# untitled2.net
KiCad netlist of a schematic drawn in EAGLE
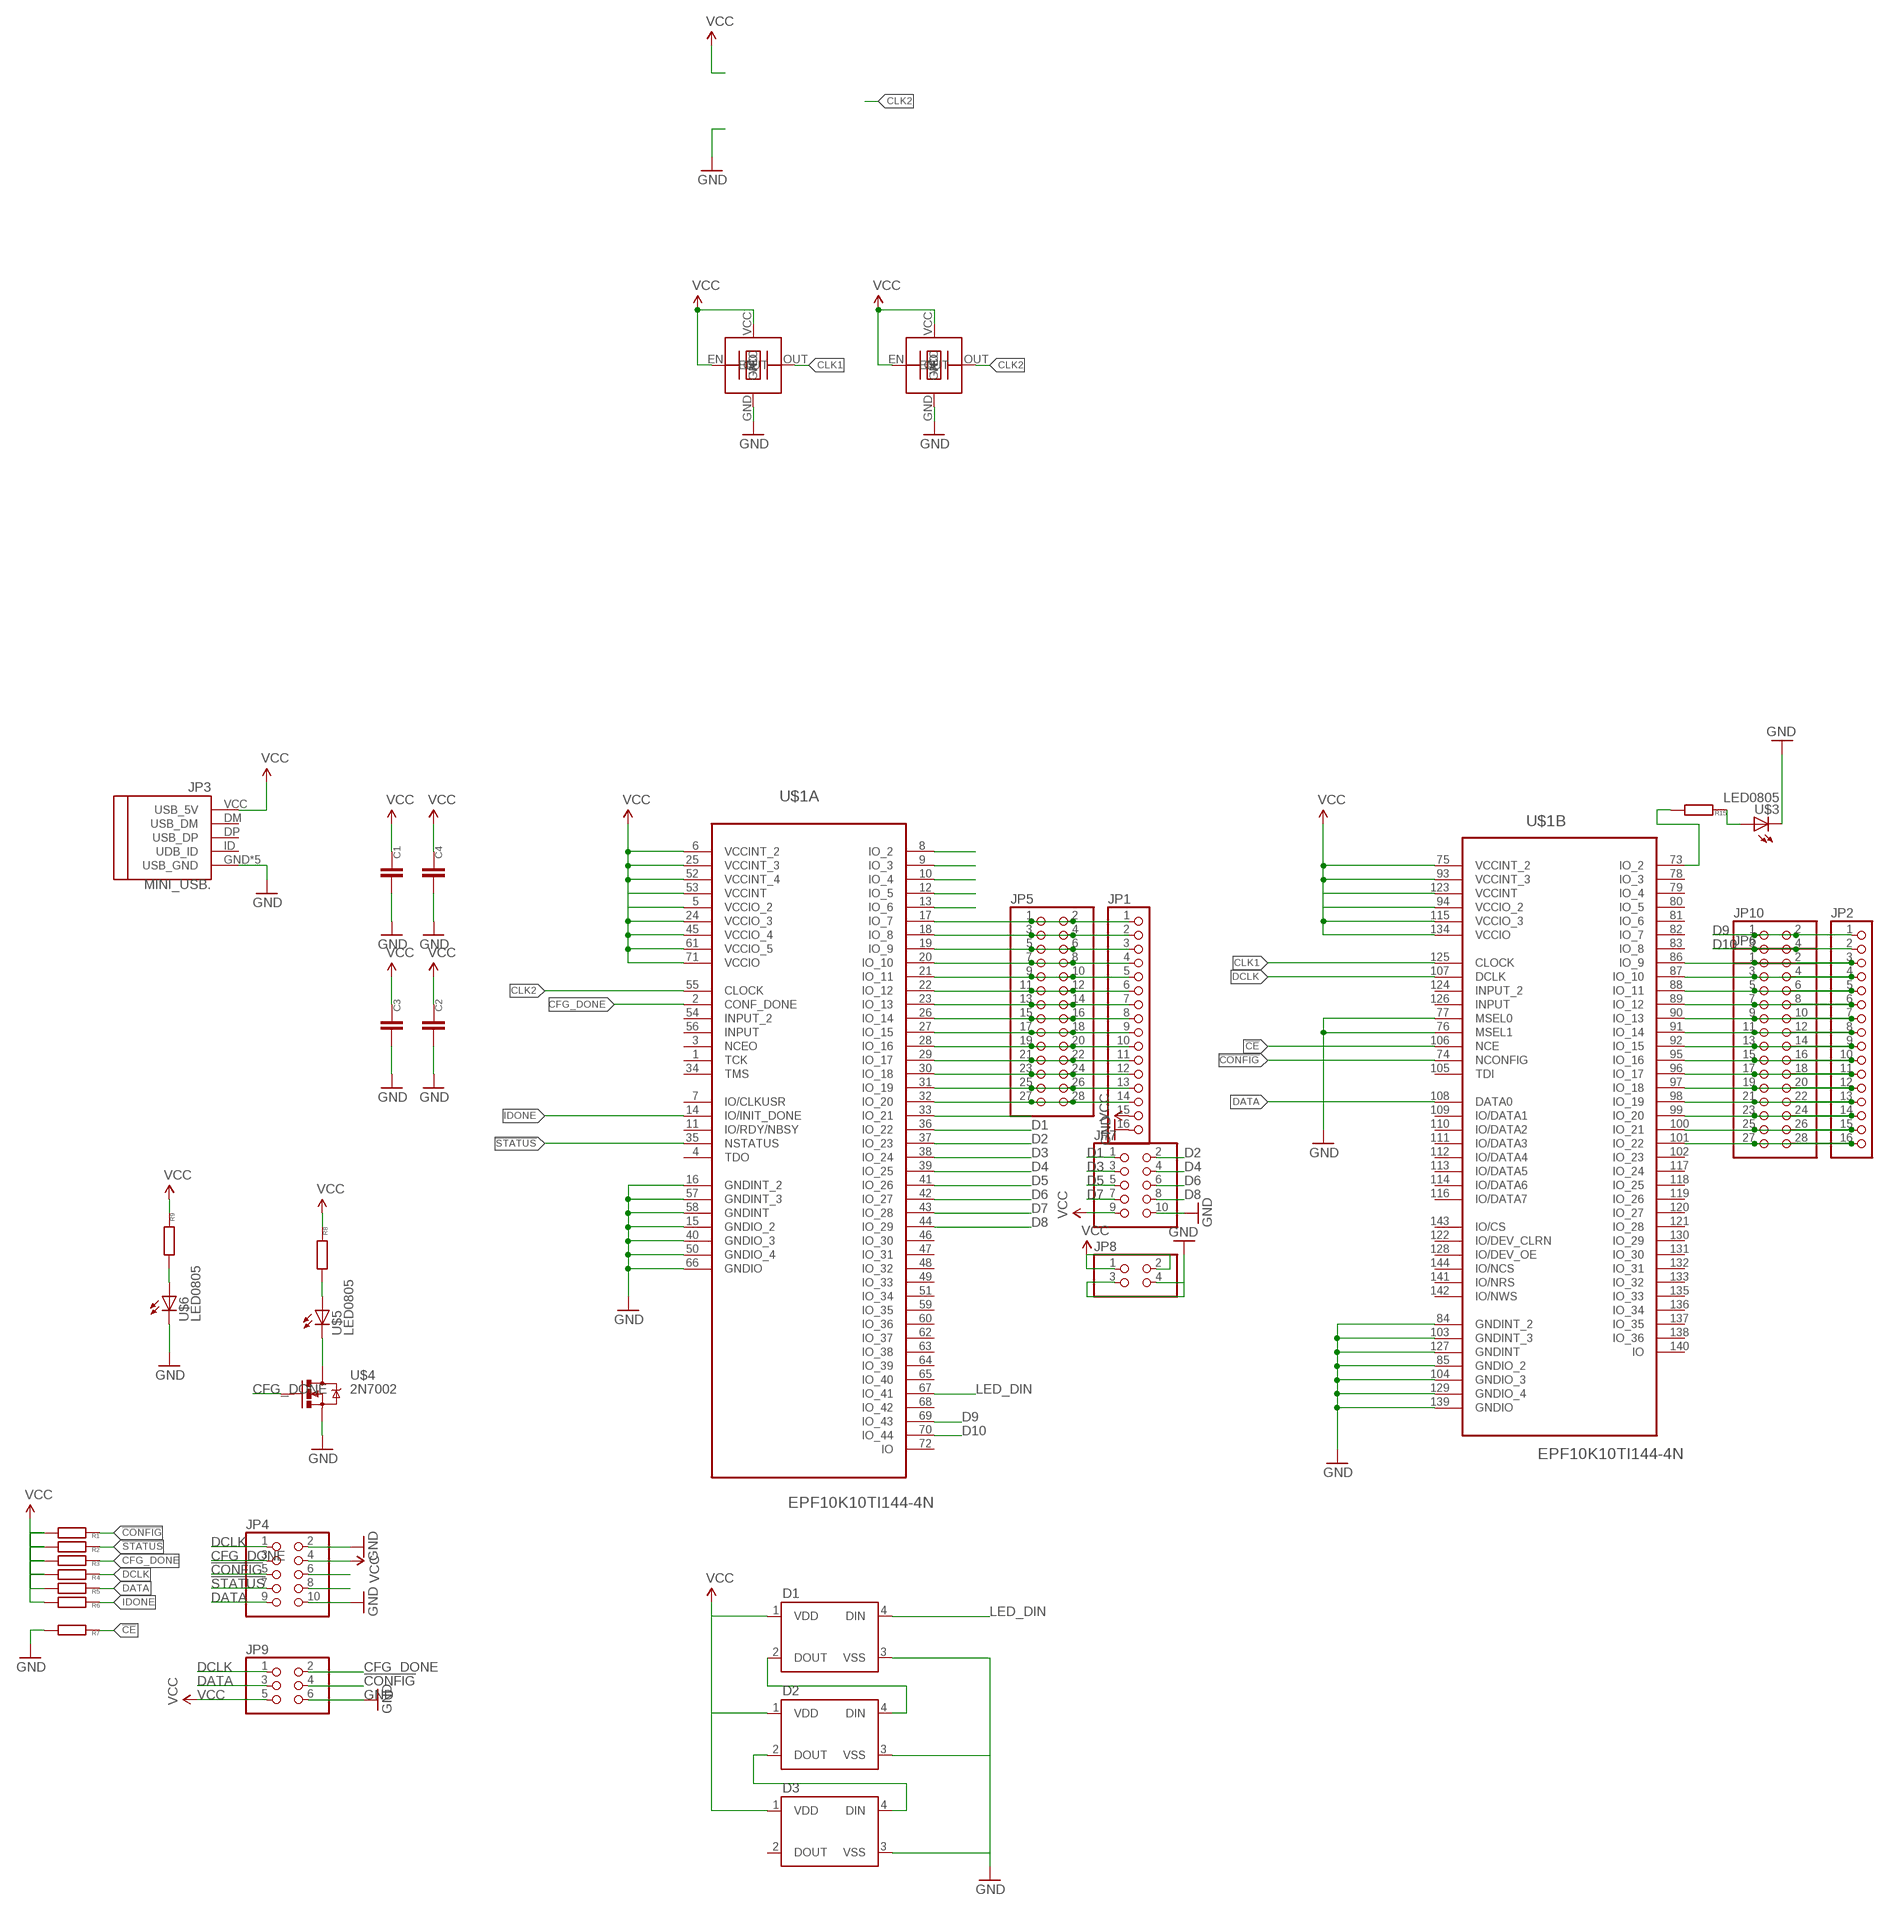
[diagram p0: schematic, sheet 1]

(export (version "E")
  (design (tool "Eeschema 10.0.6"))
  (components
    (comp (ref "C1")
      (value "CC0805")
      (footprint "eagle-import:C0805")
      (libsource (lib "eagle-import") (part "CC0805"))
    )
    (comp (ref "C2")
      (value "CC0805")
      (footprint "eagle-import:C0805")
      (libsource (lib "eagle-import") (part "CC0805"))
    )
    (comp (ref "C3")
      (value "CC0805")
      (footprint "eagle-import:C0805")
      (libsource (lib "eagle-import") (part "CC0805"))
    )
    (comp (ref "C4")
      (value "CC0805")
      (footprint "eagle-import:C0805")
      (libsource (lib "eagle-import") (part "CC0805"))
    )
    (comp (ref "D1")
      (value "WS2812B")
      (footprint "eagle-import:WS2812B")
      (libsource (lib "eagle-import") (part "WS2812B"))
    )
    (comp (ref "D2")
      (value "WS2812B")
      (footprint "eagle-import:WS2812B")
      (libsource (lib "eagle-import") (part "WS2812B"))
    )
    (comp (ref "D3")
      (value "WS2812B")
      (footprint "eagle-import:WS2812B")
      (libsource (lib "eagle-import") (part "WS2812B"))
    )
    (comp (ref "JP1")
      (value "PINHD-1X16_2.54")
      (footprint "eagle-import:1X16")
      (libsource (lib "eagle-import") (part "PINHD-1X16_2.54"))
    )
    (comp (ref "JP2")
      (value "PINHD-1X16_2.54")
      (footprint "eagle-import:1X16")
      (libsource (lib "eagle-import") (part "PINHD-1X16_2.54"))
    )
    (comp (ref "JP3")
      (value "MINI_USB.")
      (footprint "eagle-import:32005-201")
      (libsource (lib "eagle-import") (part "MINI_USB."))
    )
    (comp (ref "JP4")
      (value "PINHD-2X05_2.54-SMD")
      (footprint "eagle-import:2X05SMD")
      (libsource (lib "eagle-import") (part "PINHD-2X05_2.54-SMD"))
    )
    (comp (ref "JP5")
      (value "PINHD-2X14_2.54-SMD")
      (footprint "eagle-import:2X14SMD")
      (libsource (lib "eagle-import") (part "PINHD-2X14_2.54-SMD"))
    )
    (comp (ref "JP6")
      (value "PINHD-2X14_2.54-SMD")
      (footprint "eagle-import:2X14SMD")
      (libsource (lib "eagle-import") (part "PINHD-2X14_2.54-SMD"))
    )
    (comp (ref "JP7")
      (value "PINHD-2X05_2.54-SMD")
      (footprint "eagle-import:2X05SMD")
      (libsource (lib "eagle-import") (part "PINHD-2X05_2.54-SMD"))
    )
    (comp (ref "JP8")
      (value "PINHD-2X02_2.54-SMD")
      (footprint "eagle-import:2X02SMD")
      (libsource (lib "eagle-import") (part "PINHD-2X02_2.54-SMD"))
    )
    (comp (ref "JP9")
      (value "PINHD-2X03_2.54-SMD")
      (footprint "eagle-import:2X03SMD")
      (libsource (lib "eagle-import") (part "PINHD-2X03_2.54-SMD"))
    )
    (comp (ref "JP10")
      (value "PINHD-2X02_2.54-SMD")
      (footprint "eagle-import:2X02SMD")
      (libsource (lib "eagle-import") (part "PINHD-2X02_2.54-SMD"))
    )
    (comp (ref "R1")
      (value "R0603")
      (footprint "eagle-import:0603")
      (libsource (lib "eagle-import") (part "R0603"))
    )
    (comp (ref "R2")
      (value "R0603")
      (footprint "eagle-import:0603")
      (libsource (lib "eagle-import") (part "R0603"))
    )
    (comp (ref "R3")
      (value "R0603")
      (footprint "eagle-import:0603")
      (libsource (lib "eagle-import") (part "R0603"))
    )
    (comp (ref "R4")
      (value "R0603")
      (footprint "eagle-import:0603")
      (libsource (lib "eagle-import") (part "R0603"))
    )
    (comp (ref "R5")
      (value "R0603")
      (footprint "eagle-import:0603")
      (libsource (lib "eagle-import") (part "R0603"))
    )
    (comp (ref "R6")
      (value "R0603")
      (footprint "eagle-import:0603")
      (libsource (lib "eagle-import") (part "R0603"))
    )
    (comp (ref "R7")
      (value "R0603")
      (footprint "eagle-import:0603")
      (libsource (lib "eagle-import") (part "R0603"))
    )
    (comp (ref "R8")
      (value "R0603")
      (footprint "eagle-import:0603")
      (libsource (lib "eagle-import") (part "R0603"))
    )
    (comp (ref "R9")
      (value "R0603")
      (footprint "eagle-import:0603")
      (libsource (lib "eagle-import") (part "R0603"))
    )
    (comp (ref "R15")
      (value "R0603")
      (footprint "eagle-import:0603")
      (libsource (lib "eagle-import") (part "R0603"))
    )
    (comp (ref "U$1")
      (value "EPF10K10TI144-4N")
      (footprint "eagle-import:QFP50P2200X2200X160-144N")
      (libsource (lib "eagle-import") (part "EPF10K10TI144-4N"))
    )
    (comp (ref "U$2")
      (value "TXC-BA")
      (footprint "eagle-import:7X5")
      (libsource (lib "eagle-import") (part "TXC-BA"))
    )
    (comp (ref "U$3")
      (value "LED0805")
      (footprint "eagle-import:0805-LED")
      (libsource (lib "eagle-import") (part "LED0805"))
    )
    (comp (ref "U$4")
      (value "2N7002")
      (footprint "eagle-import:SOT23")
      (libsource (lib "eagle-import") (part "2N7002"))
    )
    (comp (ref "U$5")
      (value "LED0805")
      (footprint "eagle-import:0805-LED")
      (libsource (lib "eagle-import") (part "LED0805"))
    )
    (comp (ref "U$6")
      (value "LED0805")
      (footprint "eagle-import:0805-LED")
      (libsource (lib "eagle-import") (part "LED0805"))
    )
    (comp (ref "U$7")
      (value "TXC-BA")
      (footprint "eagle-import:7X5")
      (libsource (lib "eagle-import") (part "TXC-BA"))
    )
  )
  (nets
    (net (code "1") (name "/D1") (class "Default")
      (node (ref "JP7") (pin "1") (pinfunction "1_1") (pintype "passive"))
      (node (ref "U$1") (pin "36") (pinfunction "IO_22_36") (pintype "bidirectional"))
    )
    (net (code "2") (name "/D2") (class "Default")
      (node (ref "JP7") (pin "2") (pinfunction "2_2") (pintype "passive"))
      (node (ref "U$1") (pin "37") (pinfunction "IO_23_37") (pintype "bidirectional"))
    )
    (net (code "3") (name "/D3") (class "Default")
      (node (ref "JP7") (pin "3") (pinfunction "3_3") (pintype "passive"))
      (node (ref "U$1") (pin "38") (pinfunction "IO_24_38") (pintype "bidirectional"))
    )
    (net (code "4") (name "/D4") (class "Default")
      (node (ref "JP7") (pin "4") (pinfunction "4_4") (pintype "passive"))
      (node (ref "U$1") (pin "39") (pinfunction "IO_25_39") (pintype "bidirectional"))
    )
    (net (code "5") (name "/D5") (class "Default")
      (node (ref "JP7") (pin "5") (pinfunction "5_5") (pintype "passive"))
      (node (ref "U$1") (pin "41") (pinfunction "IO_26_41") (pintype "bidirectional"))
    )
    (net (code "6") (name "/D6") (class "Default")
      (node (ref "JP7") (pin "6") (pinfunction "6_6") (pintype "passive"))
      (node (ref "U$1") (pin "42") (pinfunction "IO_27_42") (pintype "bidirectional"))
    )
    (net (code "7") (name "/D7") (class "Default")
      (node (ref "JP7") (pin "7") (pinfunction "7_7") (pintype "passive"))
      (node (ref "U$1") (pin "43") (pinfunction "IO_28_43") (pintype "bidirectional"))
    )
    (net (code "8") (name "/D8") (class "Default")
      (node (ref "JP7") (pin "8") (pinfunction "8_8") (pintype "passive"))
      (node (ref "U$1") (pin "44") (pinfunction "IO_29_44") (pintype "bidirectional"))
    )
    (net (code "9") (name "/D9") (class "Default")
      (node (ref "JP10") (pin "1") (pinfunction "1_1") (pintype "passive"))
      (node (ref "JP10") (pin "2") (pinfunction "2_2") (pintype "passive"))
      (node (ref "JP2") (pin "1") (pinfunction "1_1") (pintype "passive"))
      (node (ref "U$1") (pin "69") (pinfunction "IO_43_69") (pintype "bidirectional"))
    )
    (net (code "10") (name "/D10") (class "Default")
      (node (ref "JP10") (pin "3") (pinfunction "3_3") (pintype "passive"))
      (node (ref "JP10") (pin "4") (pinfunction "4_4") (pintype "passive"))
      (node (ref "JP2") (pin "2") (pinfunction "2_2") (pintype "passive"))
      (node (ref "U$1") (pin "70") (pinfunction "IO_44_70") (pintype "bidirectional"))
    )
    (net (code "11") (name "/LED_DIN") (class "Default")
      (node (ref "D1") (pin "4") (pinfunction "DIN_4") (pintype "input"))
      (node (ref "U$1") (pin "67") (pinfunction "IO_41_67") (pintype "bidirectional"))
    )
    (net (code "12") (name "/~{CE}") (class "Default")
      (node (ref "R7") (pin "1") (pinfunction "1_1") (pintype "passive"))
      (node (ref "U$1") (pin "106") (pinfunction "NCE_106") (pintype "input"))
    )
    (net (code "13") (name "/~{CONFIG}") (class "Default")
      (node (ref "JP4") (pin "5") (pinfunction "5_5") (pintype "passive"))
      (node (ref "JP9") (pin "4") (pinfunction "4_4") (pintype "passive"))
      (node (ref "R1") (pin "1") (pinfunction "1_1") (pintype "passive"))
      (node (ref "U$1") (pin "74") (pinfunction "NCONFIG_74") (pintype "input"))
    )
    (net (code "14") (name "/~{STATUS}") (class "Default")
      (node (ref "JP4") (pin "7") (pinfunction "7_7") (pintype "passive"))
      (node (ref "R2") (pin "1") (pinfunction "1_1") (pintype "passive"))
      (node (ref "U$1") (pin "35") (pinfunction "NSTATUS_35") (pintype "output"))
    )
    (net (code "15") (name "CFG_DONE") (class "Default")
      (node (ref "JP4") (pin "3") (pinfunction "3_3") (pintype "passive"))
      (node (ref "JP9") (pin "2") (pinfunction "2_2") (pintype "passive"))
      (node (ref "R3") (pin "1") (pinfunction "1_1") (pintype "passive"))
      (node (ref "U$1") (pin "2") (pinfunction "CONF_DONE_2") (pintype "input"))
      (node (ref "U$4") (pin "1") (pinfunction "G_1") (pintype "passive"))
    )
    (net (code "16") (name "CLK1") (class "Default")
      (node (ref "U$1") (pin "125") (pinfunction "CLOCK_125") (pintype "input"))
      (node (ref "U$2") (pin "OUT") (pinfunction "OUT_OUT") (pintype "bidirectional"))
    )
    (net (code "17") (name "CLK2") (class "Default")
      (node (ref "U$1") (pin "55") (pinfunction "CLOCK_55") (pintype "input"))
      (node (ref "U$7") (pin "OUT") (pinfunction "OUT_OUT") (pintype "bidirectional"))
    )
    (net (code "18") (name "DATA") (class "Default")
      (node (ref "JP4") (pin "9") (pinfunction "9_9") (pintype "passive"))
      (node (ref "JP9") (pin "3") (pinfunction "3_3") (pintype "passive"))
      (node (ref "R5") (pin "1") (pinfunction "1_1") (pintype "passive"))
      (node (ref "U$1") (pin "108") (pinfunction "DATA0_108") (pintype "bidirectional"))
    )
    (net (code "19") (name "DCLK") (class "Default")
      (node (ref "JP4") (pin "1") (pinfunction "1_1") (pintype "passive"))
      (node (ref "JP9") (pin "1") (pinfunction "1_1") (pintype "passive"))
      (node (ref "R4") (pin "1") (pinfunction "1_1") (pintype "passive"))
      (node (ref "U$1") (pin "107") (pinfunction "DCLK_107") (pintype "input"))
    )
    (net (code "20") (name "GND") (class "Default")
      (node (ref "C1") (pin "1") (pinfunction "1_1") (pintype "passive"))
      (node (ref "C2") (pin "1") (pinfunction "1_1") (pintype "passive"))
      (node (ref "C3") (pin "1") (pinfunction "1_1") (pintype "passive"))
      (node (ref "C4") (pin "1") (pinfunction "1_1") (pintype "passive"))
      (node (ref "D1") (pin "3") (pinfunction "VSS_3") (pintype "power_in"))
      (node (ref "D2") (pin "3") (pinfunction "VSS_3") (pintype "power_in"))
      (node (ref "D3") (pin "3") (pinfunction "VSS_3") (pintype "power_in"))
      (node (ref "JP1") (pin "16") (pinfunction "16_16") (pintype "passive"))
      (node (ref "JP3") (pin "GND") (pinfunction "USB_GND_GND") (pintype "power_in"))
      (node (ref "JP3") (pin "M1") (pinfunction "USB_GND_M1") (pintype "power_in"))
      (node (ref "JP3") (pin "M2") (pinfunction "USB_GND_M2") (pintype "power_in"))
      (node (ref "JP3") (pin "M3") (pinfunction "USB_GND_M3") (pintype "power_in"))
      (node (ref "JP3") (pin "M4") (pinfunction "USB_GND_M4") (pintype "power_in"))
      (node (ref "JP4") (pin "10") (pinfunction "10_10") (pintype "passive"))
      (node (ref "JP4") (pin "2") (pinfunction "2_2") (pintype "passive"))
      (node (ref "JP7") (pin "10") (pinfunction "10_10") (pintype "passive"))
      (node (ref "JP8") (pin "3") (pinfunction "3_3") (pintype "passive"))
      (node (ref "JP8") (pin "4") (pinfunction "4_4") (pintype "passive"))
      (node (ref "JP9") (pin "6") (pinfunction "6_6") (pintype "passive"))
      (node (ref "R7") (pin "2") (pinfunction "2_2") (pintype "passive"))
      (node (ref "U$1") (pin "103") (pinfunction "GNDINT_3_103") (pintype "passive"))
      (node (ref "U$1") (pin "104") (pinfunction "GNDIO_3_104") (pintype "passive"))
      (node (ref "U$1") (pin "127") (pinfunction "GNDINT_127") (pintype "passive"))
      (node (ref "U$1") (pin "129") (pinfunction "GNDIO_4_129") (pintype "passive"))
      (node (ref "U$1") (pin "139") (pinfunction "GNDIO_139") (pintype "passive"))
      (node (ref "U$1") (pin "15") (pinfunction "GNDIO_2_15") (pintype "passive"))
      (node (ref "U$1") (pin "16") (pinfunction "GNDINT_2_16") (pintype "passive"))
      (node (ref "U$1") (pin "40") (pinfunction "GNDIO_3_40") (pintype "passive"))
      (node (ref "U$1") (pin "50") (pinfunction "GNDIO_4_50") (pintype "passive"))
      (node (ref "U$1") (pin "57") (pinfunction "GNDINT_3_57") (pintype "passive"))
      (node (ref "U$1") (pin "58") (pinfunction "GNDINT_58") (pintype "passive"))
      (node (ref "U$1") (pin "66") (pinfunction "GNDIO_66") (pintype "passive"))
      (node (ref "U$1") (pin "76") (pinfunction "MSEL1_76") (pintype "input"))
      (node (ref "U$1") (pin "77") (pinfunction "MSEL0_77") (pintype "input"))
      (node (ref "U$1") (pin "84") (pinfunction "GNDINT_2_84") (pintype "passive"))
      (node (ref "U$1") (pin "85") (pinfunction "GNDIO_2_85") (pintype "passive"))
      (node (ref "U$2") (pin "GND") (pinfunction "GND_GND") (pintype "bidirectional"))
      (node (ref "U$3") (pin "C") (pinfunction "C_C") (pintype "passive"))
      (node (ref "U$4") (pin "2") (pinfunction "S_2") (pintype "passive"))
      (node (ref "U$6") (pin "C") (pinfunction "C_C") (pintype "passive"))
      (node (ref "U$7") (pin "GND") (pinfunction "GND_GND") (pintype "bidirectional"))
    )
    (net (code "21") (name "IDONE") (class "Default")
      (node (ref "R6") (pin "1") (pinfunction "1_1") (pintype "passive"))
      (node (ref "U$1") (pin "14") (pinfunction "IO/INIT_DONE_14") (pintype "bidirectional"))
    )
    (net (code "22") (name "Net-(D1-DOUT)") (class "Default")
      (node (ref "D1") (pin "2") (pinfunction "DOUT_2") (pintype "output"))
      (node (ref "D2") (pin "4") (pinfunction "DIN_4") (pintype "input"))
    )
    (net (code "23") (name "Net-(D2-DOUT)") (class "Default")
      (node (ref "D2") (pin "2") (pinfunction "DOUT_2") (pintype "output"))
      (node (ref "D3") (pin "4") (pinfunction "DIN_4") (pintype "input"))
    )
    (net (code "24") (name "Net-(R8-Pad2)") (class "Default")
      (node (ref "R8") (pin "2") (pinfunction "2_2") (pintype "passive"))
      (node (ref "U$5") (pin "A") (pinfunction "A_A") (pintype "passive"))
    )
    (net (code "25") (name "Net-(R9-Pad2)") (class "Default")
      (node (ref "R9") (pin "2") (pinfunction "2_2") (pintype "passive"))
      (node (ref "U$6") (pin "A") (pinfunction "A_A") (pintype "passive"))
    )
    (net (code "26") (name "Net-(R15-Pad1)") (class "Default")
      (node (ref "R15") (pin "1") (pinfunction "1_1") (pintype "passive"))
      (node (ref "U$3") (pin "A") (pinfunction "A_A") (pintype "passive"))
    )
    (net (code "27") (name "Net-(U$1A-IO_7)") (class "Default")
      (node (ref "JP1") (pin "1") (pinfunction "1_1") (pintype "passive"))
      (node (ref "JP5") (pin "1") (pinfunction "1_1") (pintype "passive"))
      (node (ref "JP5") (pin "2") (pinfunction "2_2") (pintype "passive"))
      (node (ref "U$1") (pin "17") (pinfunction "IO_7_17") (pintype "bidirectional"))
    )
    (net (code "28") (name "Net-(U$1A-IO_8)") (class "Default")
      (node (ref "JP1") (pin "2") (pinfunction "2_2") (pintype "passive"))
      (node (ref "JP5") (pin "3") (pinfunction "3_3") (pintype "passive"))
      (node (ref "JP5") (pin "4") (pinfunction "4_4") (pintype "passive"))
      (node (ref "U$1") (pin "18") (pinfunction "IO_8_18") (pintype "bidirectional"))
    )
    (net (code "29") (name "Net-(U$1A-IO_9)") (class "Default")
      (node (ref "JP1") (pin "3") (pinfunction "3_3") (pintype "passive"))
      (node (ref "JP5") (pin "5") (pinfunction "5_5") (pintype "passive"))
      (node (ref "JP5") (pin "6") (pinfunction "6_6") (pintype "passive"))
      (node (ref "U$1") (pin "19") (pinfunction "IO_9_19") (pintype "bidirectional"))
    )
    (net (code "30") (name "Net-(U$1A-IO_10)") (class "Default")
      (node (ref "JP1") (pin "4") (pinfunction "4_4") (pintype "passive"))
      (node (ref "JP5") (pin "7") (pinfunction "7_7") (pintype "passive"))
      (node (ref "JP5") (pin "8") (pinfunction "8_8") (pintype "passive"))
      (node (ref "U$1") (pin "20") (pinfunction "IO_10_20") (pintype "bidirectional"))
    )
    (net (code "31") (name "Net-(U$1A-IO_11)") (class "Default")
      (node (ref "JP1") (pin "5") (pinfunction "5_5") (pintype "passive"))
      (node (ref "JP5") (pin "10") (pinfunction "10_10") (pintype "passive"))
      (node (ref "JP5") (pin "9") (pinfunction "9_9") (pintype "passive"))
      (node (ref "U$1") (pin "21") (pinfunction "IO_11_21") (pintype "bidirectional"))
    )
    (net (code "32") (name "Net-(U$1A-IO_12)") (class "Default")
      (node (ref "JP1") (pin "6") (pinfunction "6_6") (pintype "passive"))
      (node (ref "JP5") (pin "11") (pinfunction "11_11") (pintype "passive"))
      (node (ref "JP5") (pin "12") (pinfunction "12_12") (pintype "passive"))
      (node (ref "U$1") (pin "22") (pinfunction "IO_12_22") (pintype "bidirectional"))
    )
    (net (code "33") (name "Net-(U$1A-IO_13)") (class "Default")
      (node (ref "JP1") (pin "7") (pinfunction "7_7") (pintype "passive"))
      (node (ref "JP5") (pin "13") (pinfunction "13_13") (pintype "passive"))
      (node (ref "JP5") (pin "14") (pinfunction "14_14") (pintype "passive"))
      (node (ref "U$1") (pin "23") (pinfunction "IO_13_23") (pintype "bidirectional"))
    )
    (net (code "34") (name "Net-(U$1A-IO_14)") (class "Default")
      (node (ref "JP1") (pin "8") (pinfunction "8_8") (pintype "passive"))
      (node (ref "JP5") (pin "15") (pinfunction "15_15") (pintype "passive"))
      (node (ref "JP5") (pin "16") (pinfunction "16_16") (pintype "passive"))
      (node (ref "U$1") (pin "26") (pinfunction "IO_14_26") (pintype "bidirectional"))
    )
    (net (code "35") (name "Net-(U$1A-IO_15)") (class "Default")
      (node (ref "JP1") (pin "9") (pinfunction "9_9") (pintype "passive"))
      (node (ref "JP5") (pin "17") (pinfunction "17_17") (pintype "passive"))
      (node (ref "JP5") (pin "18") (pinfunction "18_18") (pintype "passive"))
      (node (ref "U$1") (pin "27") (pinfunction "IO_15_27") (pintype "bidirectional"))
    )
    (net (code "36") (name "Net-(U$1A-IO_16)") (class "Default")
      (node (ref "JP1") (pin "10") (pinfunction "10_10") (pintype "passive"))
      (node (ref "JP5") (pin "19") (pinfunction "19_19") (pintype "passive"))
      (node (ref "JP5") (pin "20") (pinfunction "20_20") (pintype "passive"))
      (node (ref "U$1") (pin "28") (pinfunction "IO_16_28") (pintype "bidirectional"))
    )
    (net (code "37") (name "Net-(U$1A-IO_17)") (class "Default")
      (node (ref "JP1") (pin "11") (pinfunction "11_11") (pintype "passive"))
      (node (ref "JP5") (pin "21") (pinfunction "21_21") (pintype "passive"))
      (node (ref "JP5") (pin "22") (pinfunction "22_22") (pintype "passive"))
      (node (ref "U$1") (pin "29") (pinfunction "IO_17_29") (pintype "bidirectional"))
    )
    (net (code "38") (name "Net-(U$1A-IO_18)") (class "Default")
      (node (ref "JP1") (pin "12") (pinfunction "12_12") (pintype "passive"))
      (node (ref "JP5") (pin "23") (pinfunction "23_23") (pintype "passive"))
      (node (ref "JP5") (pin "24") (pinfunction "24_24") (pintype "passive"))
      (node (ref "U$1") (pin "30") (pinfunction "IO_18_30") (pintype "bidirectional"))
    )
    (net (code "39") (name "Net-(U$1A-IO_19)") (class "Default")
      (node (ref "JP1") (pin "13") (pinfunction "13_13") (pintype "passive"))
      (node (ref "JP5") (pin "25") (pinfunction "25_25") (pintype "passive"))
      (node (ref "JP5") (pin "26") (pinfunction "26_26") (pintype "passive"))
      (node (ref "U$1") (pin "31") (pinfunction "IO_19_31") (pintype "bidirectional"))
    )
    (net (code "40") (name "Net-(U$1A-IO_20)") (class "Default")
      (node (ref "JP1") (pin "14") (pinfunction "14_14") (pintype "passive"))
      (node (ref "JP5") (pin "27") (pinfunction "27_27") (pintype "passive"))
      (node (ref "JP5") (pin "28") (pinfunction "28_28") (pintype "passive"))
      (node (ref "U$1") (pin "32") (pinfunction "IO_20_32") (pintype "bidirectional"))
    )
    (net (code "41") (name "Net-(U$1B-IO_2)") (class "Default")
      (node (ref "R15") (pin "2") (pinfunction "2_2") (pintype "passive"))
      (node (ref "U$1") (pin "73") (pinfunction "IO_2_73") (pintype "bidirectional"))
    )
    (net (code "42") (name "Net-(U$1B-IO_9)") (class "Default")
      (node (ref "JP2") (pin "3") (pinfunction "3_3") (pintype "passive"))
      (node (ref "JP6") (pin "1") (pinfunction "1_1") (pintype "passive"))
      (node (ref "JP6") (pin "2") (pinfunction "2_2") (pintype "passive"))
      (node (ref "U$1") (pin "86") (pinfunction "IO_9_86") (pintype "bidirectional"))
    )
    (net (code "43") (name "Net-(U$1B-IO_10)") (class "Default")
      (node (ref "JP2") (pin "4") (pinfunction "4_4") (pintype "passive"))
      (node (ref "JP6") (pin "3") (pinfunction "3_3") (pintype "passive"))
      (node (ref "JP6") (pin "4") (pinfunction "4_4") (pintype "passive"))
      (node (ref "U$1") (pin "87") (pinfunction "IO_10_87") (pintype "bidirectional"))
    )
    (net (code "44") (name "Net-(U$1B-IO_11)") (class "Default")
      (node (ref "JP2") (pin "5") (pinfunction "5_5") (pintype "passive"))
      (node (ref "JP6") (pin "5") (pinfunction "5_5") (pintype "passive"))
      (node (ref "JP6") (pin "6") (pinfunction "6_6") (pintype "passive"))
      (node (ref "U$1") (pin "88") (pinfunction "IO_11_88") (pintype "bidirectional"))
    )
    (net (code "45") (name "Net-(U$1B-IO_12)") (class "Default")
      (node (ref "JP2") (pin "6") (pinfunction "6_6") (pintype "passive"))
      (node (ref "JP6") (pin "7") (pinfunction "7_7") (pintype "passive"))
      (node (ref "JP6") (pin "8") (pinfunction "8_8") (pintype "passive"))
      (node (ref "U$1") (pin "89") (pinfunction "IO_12_89") (pintype "bidirectional"))
    )
    (net (code "46") (name "Net-(U$1B-IO_13)") (class "Default")
      (node (ref "JP2") (pin "7") (pinfunction "7_7") (pintype "passive"))
      (node (ref "JP6") (pin "10") (pinfunction "10_10") (pintype "passive"))
      (node (ref "JP6") (pin "9") (pinfunction "9_9") (pintype "passive"))
      (node (ref "U$1") (pin "90") (pinfunction "IO_13_90") (pintype "bidirectional"))
    )
    (net (code "47") (name "Net-(U$1B-IO_14)") (class "Default")
      (node (ref "JP2") (pin "8") (pinfunction "8_8") (pintype "passive"))
      (node (ref "JP6") (pin "11") (pinfunction "11_11") (pintype "passive"))
      (node (ref "JP6") (pin "12") (pinfunction "12_12") (pintype "passive"))
      (node (ref "U$1") (pin "91") (pinfunction "IO_14_91") (pintype "bidirectional"))
    )
    (net (code "48") (name "Net-(U$1B-IO_15)") (class "Default")
      (node (ref "JP2") (pin "9") (pinfunction "9_9") (pintype "passive"))
      (node (ref "JP6") (pin "13") (pinfunction "13_13") (pintype "passive"))
      (node (ref "JP6") (pin "14") (pinfunction "14_14") (pintype "passive"))
      (node (ref "U$1") (pin "92") (pinfunction "IO_15_92") (pintype "bidirectional"))
    )
    (net (code "49") (name "Net-(U$1B-IO_16)") (class "Default")
      (node (ref "JP2") (pin "10") (pinfunction "10_10") (pintype "passive"))
      (node (ref "JP6") (pin "15") (pinfunction "15_15") (pintype "passive"))
      (node (ref "JP6") (pin "16") (pinfunction "16_16") (pintype "passive"))
      (node (ref "U$1") (pin "95") (pinfunction "IO_16_95") (pintype "bidirectional"))
    )
    (net (code "50") (name "Net-(U$1B-IO_17)") (class "Default")
      (node (ref "JP2") (pin "11") (pinfunction "11_11") (pintype "passive"))
      (node (ref "JP6") (pin "17") (pinfunction "17_17") (pintype "passive"))
      (node (ref "JP6") (pin "18") (pinfunction "18_18") (pintype "passive"))
      (node (ref "U$1") (pin "96") (pinfunction "IO_17_96") (pintype "bidirectional"))
    )
    (net (code "51") (name "Net-(U$1B-IO_18)") (class "Default")
      (node (ref "JP2") (pin "12") (pinfunction "12_12") (pintype "passive"))
      (node (ref "JP6") (pin "19") (pinfunction "19_19") (pintype "passive"))
      (node (ref "JP6") (pin "20") (pinfunction "20_20") (pintype "passive"))
      (node (ref "U$1") (pin "97") (pinfunction "IO_18_97") (pintype "bidirectional"))
    )
    (net (code "52") (name "Net-(U$1B-IO_19)") (class "Default")
      (node (ref "JP2") (pin "13") (pinfunction "13_13") (pintype "passive"))
      (node (ref "JP6") (pin "21") (pinfunction "21_21") (pintype "passive"))
      (node (ref "JP6") (pin "22") (pinfunction "22_22") (pintype "passive"))
      (node (ref "U$1") (pin "98") (pinfunction "IO_19_98") (pintype "bidirectional"))
    )
    (net (code "53") (name "Net-(U$1B-IO_20)") (class "Default")
      (node (ref "JP2") (pin "14") (pinfunction "14_14") (pintype "passive"))
      (node (ref "JP6") (pin "23") (pinfunction "23_23") (pintype "passive"))
      (node (ref "JP6") (pin "24") (pinfunction "24_24") (pintype "passive"))
      (node (ref "U$1") (pin "99") (pinfunction "IO_20_99") (pintype "bidirectional"))
    )
    (net (code "54") (name "Net-(U$1B-IO_21)") (class "Default")
      (node (ref "JP2") (pin "15") (pinfunction "15_15") (pintype "passive"))
      (node (ref "JP6") (pin "25") (pinfunction "25_25") (pintype "passive"))
      (node (ref "JP6") (pin "26") (pinfunction "26_26") (pintype "passive"))
      (node (ref "U$1") (pin "100") (pinfunction "IO_21_100") (pintype "bidirectional"))
    )
    (net (code "55") (name "Net-(U$1B-IO_22)") (class "Default")
      (node (ref "JP2") (pin "16") (pinfunction "16_16") (pintype "passive"))
      (node (ref "JP6") (pin "27") (pinfunction "27_27") (pintype "passive"))
      (node (ref "JP6") (pin "28") (pinfunction "28_28") (pintype "passive"))
      (node (ref "U$1") (pin "101") (pinfunction "IO_22_101") (pintype "bidirectional"))
    )
    (net (code "56") (name "Net-(U$4-D)") (class "Default")
      (node (ref "U$4") (pin "3") (pinfunction "D_3") (pintype "passive"))
      (node (ref "U$5") (pin "C") (pinfunction "C_C") (pintype "passive"))
    )
    (net (code "57") (name "VCC") (class "Default")
      (node (ref "C1") (pin "2") (pinfunction "2_2") (pintype "passive"))
      (node (ref "C2") (pin "2") (pinfunction "2_2") (pintype "passive"))
      (node (ref "C3") (pin "2") (pinfunction "2_2") (pintype "passive"))
      (node (ref "C4") (pin "2") (pinfunction "2_2") (pintype "passive"))
      (node (ref "D1") (pin "1") (pinfunction "VDD_1") (pintype "power_in"))
      (node (ref "D2") (pin "1") (pinfunction "VDD_1") (pintype "power_in"))
      (node (ref "D3") (pin "1") (pinfunction "VDD_1") (pintype "power_in"))
      (node (ref "JP1") (pin "15") (pinfunction "15_15") (pintype "passive"))
      (node (ref "JP3") (pin "VCC") (pinfunction "USB_5V_VCC") (pintype "power_in"))
      (node (ref "JP4") (pin "4") (pinfunction "4_4") (pintype "passive"))
      (node (ref "JP7") (pin "9") (pinfunction "9_9") (pintype "passive"))
      (node (ref "JP8") (pin "1") (pinfunction "1_1") (pintype "passive"))
      (node (ref "JP8") (pin "2") (pinfunction "2_2") (pintype "passive"))
      (node (ref "JP9") (pin "5") (pinfunction "5_5") (pintype "passive"))
      (node (ref "R1") (pin "2") (pinfunction "2_2") (pintype "passive"))
      (node (ref "R2") (pin "2") (pinfunction "2_2") (pintype "passive"))
      (node (ref "R3") (pin "2") (pinfunction "2_2") (pintype "passive"))
      (node (ref "R4") (pin "2") (pinfunction "2_2") (pintype "passive"))
      (node (ref "R5") (pin "2") (pinfunction "2_2") (pintype "passive"))
      (node (ref "R6") (pin "2") (pinfunction "2_2") (pintype "passive"))
      (node (ref "R8") (pin "1") (pinfunction "1_1") (pintype "passive"))
      (node (ref "R9") (pin "1") (pinfunction "1_1") (pintype "passive"))
      (node (ref "U$1") (pin "115") (pinfunction "VCCIO_3_115") (pintype "power_in"))
      (node (ref "U$1") (pin "123") (pinfunction "VCCINT_123") (pintype "power_in"))
      (node (ref "U$1") (pin "134") (pinfunction "VCCIO_134") (pintype "power_in"))
      (node (ref "U$1") (pin "24") (pinfunction "VCCIO_3_24") (pintype "power_in"))
      (node (ref "U$1") (pin "25") (pinfunction "VCCINT_3_25") (pintype "power_in"))
      (node (ref "U$1") (pin "45") (pinfunction "VCCIO_4_45") (pintype "power_in"))
      (node (ref "U$1") (pin "5") (pinfunction "VCCIO_2_5") (pintype "power_in"))
      (node (ref "U$1") (pin "52") (pinfunction "VCCINT_4_52") (pintype "power_in"))
      (node (ref "U$1") (pin "53") (pinfunction "VCCINT_53") (pintype "power_in"))
      (node (ref "U$1") (pin "6") (pinfunction "VCCINT_2_6") (pintype "power_in"))
      (node (ref "U$1") (pin "61") (pinfunction "VCCIO_5_61") (pintype "power_in"))
      (node (ref "U$1") (pin "71") (pinfunction "VCCIO_71") (pintype "power_in"))
      (node (ref "U$1") (pin "75") (pinfunction "VCCINT_2_75") (pintype "power_in"))
      (node (ref "U$1") (pin "93") (pinfunction "VCCINT_3_93") (pintype "power_in"))
      (node (ref "U$1") (pin "94") (pinfunction "VCCIO_2_94") (pintype "power_in"))
      (node (ref "U$2") (pin "EN") (pinfunction "EN_EN") (pintype "bidirectional"))
      (node (ref "U$2") (pin "VCC") (pinfunction "VCC_VCC") (pintype "bidirectional"))
      (node (ref "U$7") (pin "EN") (pinfunction "EN_EN") (pintype "bidirectional"))
      (node (ref "U$7") (pin "VCC") (pinfunction "VCC_VCC") (pintype "bidirectional"))
    )
    (net (code "58") (name "unconnected-(D3-DOUT-Pad2)") (class "Default")
      (node (ref "D3") (pin "2") (pinfunction "DOUT_2") (pintype "output"))
    )
    (net (code "59") (name "unconnected-(JP3-UDB_ID-PadID)") (class "Default")
      (node (ref "JP3") (pin "ID") (pinfunction "UDB_ID_ID") (pintype "bidirectional"))
    )
    (net (code "60") (name "unconnected-(JP3-USB_DM-PadDM)") (class "Default")
      (node (ref "JP3") (pin "DM") (pinfunction "USB_DM_DM") (pintype "bidirectional"))
    )
    (net (code "61") (name "unconnected-(JP3-USB_DP-PadDP)") (class "Default")
      (node (ref "JP3") (pin "DP") (pinfunction "USB_DP_DP") (pintype "bidirectional"))
    )
    (net (code "62") (name "unconnected-(JP4-Pad6)") (class "Default")
      (node (ref "JP4") (pin "6") (pinfunction "6_6") (pintype "passive"))
    )
    (net (code "63") (name "unconnected-(JP4-Pad8)") (class "Default")
      (node (ref "JP4") (pin "8") (pinfunction "8_8") (pintype "passive"))
    )
    (net (code "64") (name "unconnected-(U$1A-INPUT-Pad56)") (class "Default")
      (node (ref "U$1") (pin "56") (pinfunction "INPUT_56") (pintype "input"))
    )
    (net (code "65") (name "unconnected-(U$1A-INPUT_2-Pad54)") (class "Default")
      (node (ref "U$1") (pin "54") (pinfunction "INPUT_2_54") (pintype "input"))
    )
    (net (code "66") (name "unconnected-(U$1A-IO-Pad72)") (class "Default")
      (node (ref "U$1") (pin "72") (pinfunction "IO_72") (pintype "bidirectional"))
    )
    (net (code "67") (name "unconnected-(U$1A-IO_2-Pad8)") (class "Default")
      (node (ref "U$1") (pin "8") (pinfunction "IO_2_8") (pintype "bidirectional"))
    )
    (net (code "68") (name "unconnected-(U$1A-IO_3-Pad9)") (class "Default")
      (node (ref "U$1") (pin "9") (pinfunction "IO_3_9") (pintype "bidirectional"))
    )
    (net (code "69") (name "unconnected-(U$1A-IO_4-Pad10)") (class "Default")
      (node (ref "U$1") (pin "10") (pinfunction "IO_4_10") (pintype "bidirectional"))
    )
    (net (code "70") (name "unconnected-(U$1A-IO_5-Pad12)") (class "Default")
      (node (ref "U$1") (pin "12") (pinfunction "IO_5_12") (pintype "bidirectional"))
    )
    (net (code "71") (name "unconnected-(U$1A-IO_6-Pad13)") (class "Default")
      (node (ref "U$1") (pin "13") (pinfunction "IO_6_13") (pintype "bidirectional"))
    )
    (net (code "72") (name "unconnected-(U$1A-IO_21-Pad33)") (class "Default")
      (node (ref "U$1") (pin "33") (pinfunction "IO_21_33") (pintype "bidirectional"))
    )
    (net (code "73") (name "unconnected-(U$1A-IO_30-Pad46)") (class "Default")
      (node (ref "U$1") (pin "46") (pinfunction "IO_30_46") (pintype "bidirectional"))
    )
    (net (code "74") (name "unconnected-(U$1A-IO_31-Pad47)") (class "Default")
      (node (ref "U$1") (pin "47") (pinfunction "IO_31_47") (pintype "bidirectional"))
    )
    (net (code "75") (name "unconnected-(U$1A-IO_32-Pad48)") (class "Default")
      (node (ref "U$1") (pin "48") (pinfunction "IO_32_48") (pintype "bidirectional"))
    )
    (net (code "76") (name "unconnected-(U$1A-IO_33-Pad49)") (class "Default")
      (node (ref "U$1") (pin "49") (pinfunction "IO_33_49") (pintype "bidirectional"))
    )
    (net (code "77") (name "unconnected-(U$1A-IO_34-Pad51)") (class "Default")
      (node (ref "U$1") (pin "51") (pinfunction "IO_34_51") (pintype "bidirectional"))
    )
    (net (code "78") (name "unconnected-(U$1A-IO_35-Pad59)") (class "Default")
      (node (ref "U$1") (pin "59") (pinfunction "IO_35_59") (pintype "bidirectional"))
    )
    (net (code "79") (name "unconnected-(U$1A-IO_36-Pad60)") (class "Default")
      (node (ref "U$1") (pin "60") (pinfunction "IO_36_60") (pintype "bidirectional"))
    )
    (net (code "80") (name "unconnected-(U$1A-IO_37-Pad62)") (class "Default")
      (node (ref "U$1") (pin "62") (pinfunction "IO_37_62") (pintype "bidirectional"))
    )
    (net (code "81") (name "unconnected-(U$1A-IO_38-Pad63)") (class "Default")
      (node (ref "U$1") (pin "63") (pinfunction "IO_38_63") (pintype "bidirectional"))
    )
    (net (code "82") (name "unconnected-(U$1A-IO_39-Pad64)") (class "Default")
      (node (ref "U$1") (pin "64") (pinfunction "IO_39_64") (pintype "bidirectional"))
    )
    (net (code "83") (name "unconnected-(U$1A-IO_40-Pad65)") (class "Default")
      (node (ref "U$1") (pin "65") (pinfunction "IO_40_65") (pintype "bidirectional"))
    )
    (net (code "84") (name "unconnected-(U$1A-IO_42-Pad68)") (class "Default")
      (node (ref "U$1") (pin "68") (pinfunction "IO_42_68") (pintype "bidirectional"))
    )
    (net (code "85") (name "unconnected-(U$1A-IO{slash}CLKUSR-Pad7)") (class "Default")
      (node (ref "U$1") (pin "7") (pinfunction "IO/CLKUSR_7") (pintype "bidirectional"))
    )
    (net (code "86") (name "unconnected-(U$1A-IO{slash}RDY{slash}NBSY-Pad11)") (class "Default")
      (node (ref "U$1") (pin "11") (pinfunction "IO/RDY/NBSY_11") (pintype "bidirectional"))
    )
    (net (code "87") (name "unconnected-(U$1A-NCEO-Pad3)") (class "Default")
      (node (ref "U$1") (pin "3") (pinfunction "NCEO_3") (pintype "input"))
    )
    (net (code "88") (name "unconnected-(U$1A-TCK-Pad1)") (class "Default")
      (node (ref "U$1") (pin "1") (pinfunction "TCK_1") (pintype "input"))
    )
    (net (code "89") (name "unconnected-(U$1A-TDO-Pad4)") (class "Default")
      (node (ref "U$1") (pin "4") (pinfunction "TDO_4") (pintype "output"))
    )
    (net (code "90") (name "unconnected-(U$1A-TMS-Pad34)") (class "Default")
      (node (ref "U$1") (pin "34") (pinfunction "TMS_34") (pintype "input"))
    )
    (net (code "91") (name "unconnected-(U$1B-INPUT-Pad126)") (class "Default")
      (node (ref "U$1") (pin "126") (pinfunction "INPUT_126") (pintype "input"))
    )
    (net (code "92") (name "unconnected-(U$1B-INPUT_2-Pad124)") (class "Default")
      (node (ref "U$1") (pin "124") (pinfunction "INPUT_2_124") (pintype "input"))
    )
    (net (code "93") (name "unconnected-(U$1B-IO-Pad140)") (class "Default")
      (node (ref "U$1") (pin "140") (pinfunction "IO_140") (pintype "bidirectional"))
    )
    (net (code "94") (name "unconnected-(U$1B-IO_3-Pad78)") (class "Default")
      (node (ref "U$1") (pin "78") (pinfunction "IO_3_78") (pintype "bidirectional"))
    )
    (net (code "95") (name "unconnected-(U$1B-IO_4-Pad79)") (class "Default")
      (node (ref "U$1") (pin "79") (pinfunction "IO_4_79") (pintype "bidirectional"))
    )
    (net (code "96") (name "unconnected-(U$1B-IO_5-Pad80)") (class "Default")
      (node (ref "U$1") (pin "80") (pinfunction "IO_5_80") (pintype "bidirectional"))
    )
    (net (code "97") (name "unconnected-(U$1B-IO_6-Pad81)") (class "Default")
      (node (ref "U$1") (pin "81") (pinfunction "IO_6_81") (pintype "bidirectional"))
    )
    (net (code "98") (name "unconnected-(U$1B-IO_7-Pad82)") (class "Default")
      (node (ref "U$1") (pin "82") (pinfunction "IO_7_82") (pintype "bidirectional"))
    )
    (net (code "99") (name "unconnected-(U$1B-IO_8-Pad83)") (class "Default")
      (node (ref "U$1") (pin "83") (pinfunction "IO_8_83") (pintype "bidirectional"))
    )
    (net (code "100") (name "unconnected-(U$1B-IO_23-Pad102)") (class "Default")
      (node (ref "U$1") (pin "102") (pinfunction "IO_23_102") (pintype "bidirectional"))
    )
    (net (code "101") (name "unconnected-(U$1B-IO_24-Pad117)") (class "Default")
      (node (ref "U$1") (pin "117") (pinfunction "IO_24_117") (pintype "bidirectional"))
    )
    (net (code "102") (name "unconnected-(U$1B-IO_25-Pad118)") (class "Default")
      (node (ref "U$1") (pin "118") (pinfunction "IO_25_118") (pintype "bidirectional"))
    )
    (net (code "103") (name "unconnected-(U$1B-IO_26-Pad119)") (class "Default")
      (node (ref "U$1") (pin "119") (pinfunction "IO_26_119") (pintype "bidirectional"))
    )
    (net (code "104") (name "unconnected-(U$1B-IO_27-Pad120)") (class "Default")
      (node (ref "U$1") (pin "120") (pinfunction "IO_27_120") (pintype "bidirectional"))
    )
    (net (code "105") (name "unconnected-(U$1B-IO_28-Pad121)") (class "Default")
      (node (ref "U$1") (pin "121") (pinfunction "IO_28_121") (pintype "bidirectional"))
    )
    (net (code "106") (name "unconnected-(U$1B-IO_29-Pad130)") (class "Default")
      (node (ref "U$1") (pin "130") (pinfunction "IO_29_130") (pintype "bidirectional"))
    )
    (net (code "107") (name "unconnected-(U$1B-IO_30-Pad131)") (class "Default")
      (node (ref "U$1") (pin "131") (pinfunction "IO_30_131") (pintype "bidirectional"))
    )
    (net (code "108") (name "unconnected-(U$1B-IO_31-Pad132)") (class "Default")
      (node (ref "U$1") (pin "132") (pinfunction "IO_31_132") (pintype "bidirectional"))
    )
    (net (code "109") (name "unconnected-(U$1B-IO_32-Pad133)") (class "Default")
      (node (ref "U$1") (pin "133") (pinfunction "IO_32_133") (pintype "bidirectional"))
    )
    (net (code "110") (name "unconnected-(U$1B-IO_33-Pad135)") (class "Default")
      (node (ref "U$1") (pin "135") (pinfunction "IO_33_135") (pintype "bidirectional"))
    )
    (net (code "111") (name "unconnected-(U$1B-IO_34-Pad136)") (class "Default")
      (node (ref "U$1") (pin "136") (pinfunction "IO_34_136") (pintype "bidirectional"))
    )
    (net (code "112") (name "unconnected-(U$1B-IO_35-Pad137)") (class "Default")
      (node (ref "U$1") (pin "137") (pinfunction "IO_35_137") (pintype "bidirectional"))
    )
    (net (code "113") (name "unconnected-(U$1B-IO_36-Pad138)") (class "Default")
      (node (ref "U$1") (pin "138") (pinfunction "IO_36_138") (pintype "bidirectional"))
    )
    (net (code "114") (name "unconnected-(U$1B-IO{slash}CS-Pad143)") (class "Default")
      (node (ref "U$1") (pin "143") (pinfunction "IO/CS_143") (pintype "bidirectional"))
    )
    (net (code "115") (name "unconnected-(U$1B-IO{slash}DATA1-Pad109)") (class "Default")
      (node (ref "U$1") (pin "109") (pinfunction "IO/DATA1_109") (pintype "bidirectional"))
    )
    (net (code "116") (name "unconnected-(U$1B-IO{slash}DATA2-Pad110)") (class "Default")
      (node (ref "U$1") (pin "110") (pinfunction "IO/DATA2_110") (pintype "bidirectional"))
    )
    (net (code "117") (name "unconnected-(U$1B-IO{slash}DATA3-Pad111)") (class "Default")
      (node (ref "U$1") (pin "111") (pinfunction "IO/DATA3_111") (pintype "bidirectional"))
    )
    (net (code "118") (name "unconnected-(U$1B-IO{slash}DATA4-Pad112)") (class "Default")
      (node (ref "U$1") (pin "112") (pinfunction "IO/DATA4_112") (pintype "bidirectional"))
    )
    (net (code "119") (name "unconnected-(U$1B-IO{slash}DATA5-Pad113)") (class "Default")
      (node (ref "U$1") (pin "113") (pinfunction "IO/DATA5_113") (pintype "bidirectional"))
    )
    (net (code "120") (name "unconnected-(U$1B-IO{slash}DATA6-Pad114)") (class "Default")
      (node (ref "U$1") (pin "114") (pinfunction "IO/DATA6_114") (pintype "bidirectional"))
    )
    (net (code "121") (name "unconnected-(U$1B-IO{slash}DATA7-Pad116)") (class "Default")
      (node (ref "U$1") (pin "116") (pinfunction "IO/DATA7_116") (pintype "bidirectional"))
    )
    (net (code "122") (name "unconnected-(U$1B-IO{slash}DEV_CLRN-Pad122)") (class "Default")
      (node (ref "U$1") (pin "122") (pinfunction "IO/DEV_CLRN_122") (pintype "bidirectional"))
    )
    (net (code "123") (name "unconnected-(U$1B-IO{slash}DEV_OE-Pad128)") (class "Default")
      (node (ref "U$1") (pin "128") (pinfunction "IO/DEV_OE_128") (pintype "bidirectional"))
    )
    (net (code "124") (name "unconnected-(U$1B-IO{slash}NCS-Pad144)") (class "Default")
      (node (ref "U$1") (pin "144") (pinfunction "IO/NCS_144") (pintype "bidirectional"))
    )
    (net (code "125") (name "unconnected-(U$1B-IO{slash}NRS-Pad141)") (class "Default")
      (node (ref "U$1") (pin "141") (pinfunction "IO/NRS_141") (pintype "bidirectional"))
    )
    (net (code "126") (name "unconnected-(U$1B-IO{slash}NWS-Pad142)") (class "Default")
      (node (ref "U$1") (pin "142") (pinfunction "IO/NWS_142") (pintype "bidirectional"))
    )
    (net (code "127") (name "unconnected-(U$1B-TDI-Pad105)") (class "Default")
      (node (ref "U$1") (pin "105") (pinfunction "TDI_105") (pintype "input"))
    )
  )
)
